# table2.net
KiCad netlist of a schematic drawn in EasyEDA
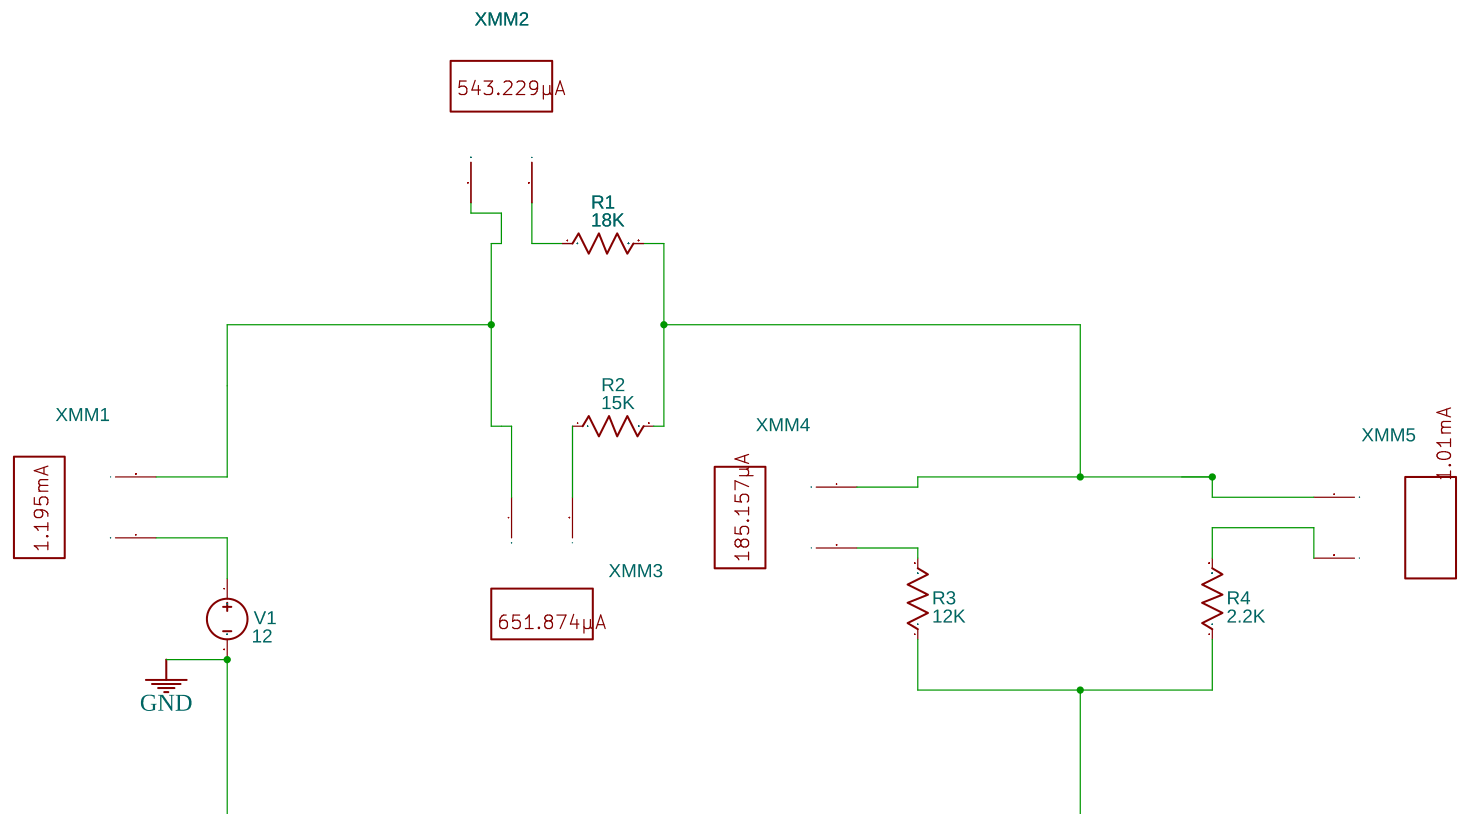
[diagram p0: schematic sheet]

(export (version "E")
  (design (tool "Eeschema 10.0.6"))
  (components
    (comp (ref "R1") (value "18K") (libsource (lib "") (part "Resistor_US_1")))
    (comp (ref "R2") (value "15K") (libsource (lib "") (part "Resistor_US_1")))
    (comp (ref "R3") (value "12K") (libsource (lib "") (part "Resistor_US")))
    (comp (ref "R4") (value "2.2K") (libsource (lib "") (part "Resistor_US")))
    (comp (ref "V1") (value "12") (libsource (lib "") (part "VDC")))
    (comp (ref "XMM1") (value "Multimeter") (libsource (lib "") (part "MULTIMETER_4")))
    (comp (ref "XMM2") (value "Multimeter") (libsource (lib "") (part "MULTIMETER_2")))
    (comp (ref "XMM3") (value "Multimeter") (libsource (lib "") (part "MULTIMETER_1")))
    (comp (ref "XMM4") (value "Multimeter") (libsource (lib "") (part "MULTIMETER")))
    (comp (ref "XMM5") (value "Multimeter") (libsource (lib "") (part "MULTIMETER_3")))
  )
  (nets
    (net (code "1") (name "GND") (class "Default")
      (node (ref "R3") (pin "1") (pinfunction "1_1") (pintype "unspecified"))
      (node (ref "R4") (pin "1") (pinfunction "1_1") (pintype "unspecified"))
      (node (ref "V1") (pin "2") (pinfunction "2_2") (pintype "unspecified"))
    )
    (net (code "2") (name "Net-(XMM1-+)") (class "Default")
      (node (ref "V1") (pin "1") (pinfunction "1_1") (pintype "unspecified"))
      (node (ref "XMM1") (pin "1") (pinfunction "+_1") (pintype "unspecified"))
    )
    (net (code "3") (name "Net-(XMM1-I)") (class "Default")
      (node (ref "XMM1") (pin "2") (pinfunction "I_2") (pintype "unspecified"))
      (node (ref "XMM2") (pin "1") (pinfunction "+_1") (pintype "unspecified"))
      (node (ref "XMM3") (pin "1") (pinfunction "+_1") (pintype "unspecified"))
    )
    (net (code "4") (name "Net-(XMM2-I)") (class "Default")
      (node (ref "R1") (pin "1") (pinfunction "1_1") (pintype "unspecified"))
      (node (ref "XMM2") (pin "2") (pinfunction "I_2") (pintype "unspecified"))
    )
    (net (code "5") (name "Net-(XMM3-I)") (class "Default")
      (node (ref "R2") (pin "1") (pinfunction "1_1") (pintype "unspecified"))
      (node (ref "XMM3") (pin "2") (pinfunction "I_2") (pintype "unspecified"))
    )
    (net (code "6") (name "Net-(XMM4-+)") (class "Default")
      (node (ref "R1") (pin "2") (pinfunction "2_2") (pintype "unspecified"))
      (node (ref "R2") (pin "2") (pinfunction "2_2") (pintype "unspecified"))
      (node (ref "XMM4") (pin "1") (pinfunction "+_1") (pintype "unspecified"))
      (node (ref "XMM5") (pin "1") (pinfunction "+_1") (pintype "unspecified"))
    )
    (net (code "7") (name "Net-(XMM4-I)") (class "Default")
      (node (ref "R3") (pin "2") (pinfunction "2_2") (pintype "unspecified"))
      (node (ref "XMM4") (pin "2") (pinfunction "I_2") (pintype "unspecified"))
    )
    (net (code "8") (name "Net-(XMM5-I)") (class "Default")
      (node (ref "R4") (pin "2") (pinfunction "2_2") (pintype "unspecified"))
      (node (ref "XMM5") (pin "2") (pinfunction "I_2") (pintype "unspecified"))
    )
  )
)
